# 04_-_RADIO.net
KiCad netlist of a schematic drawn in Altium Designer
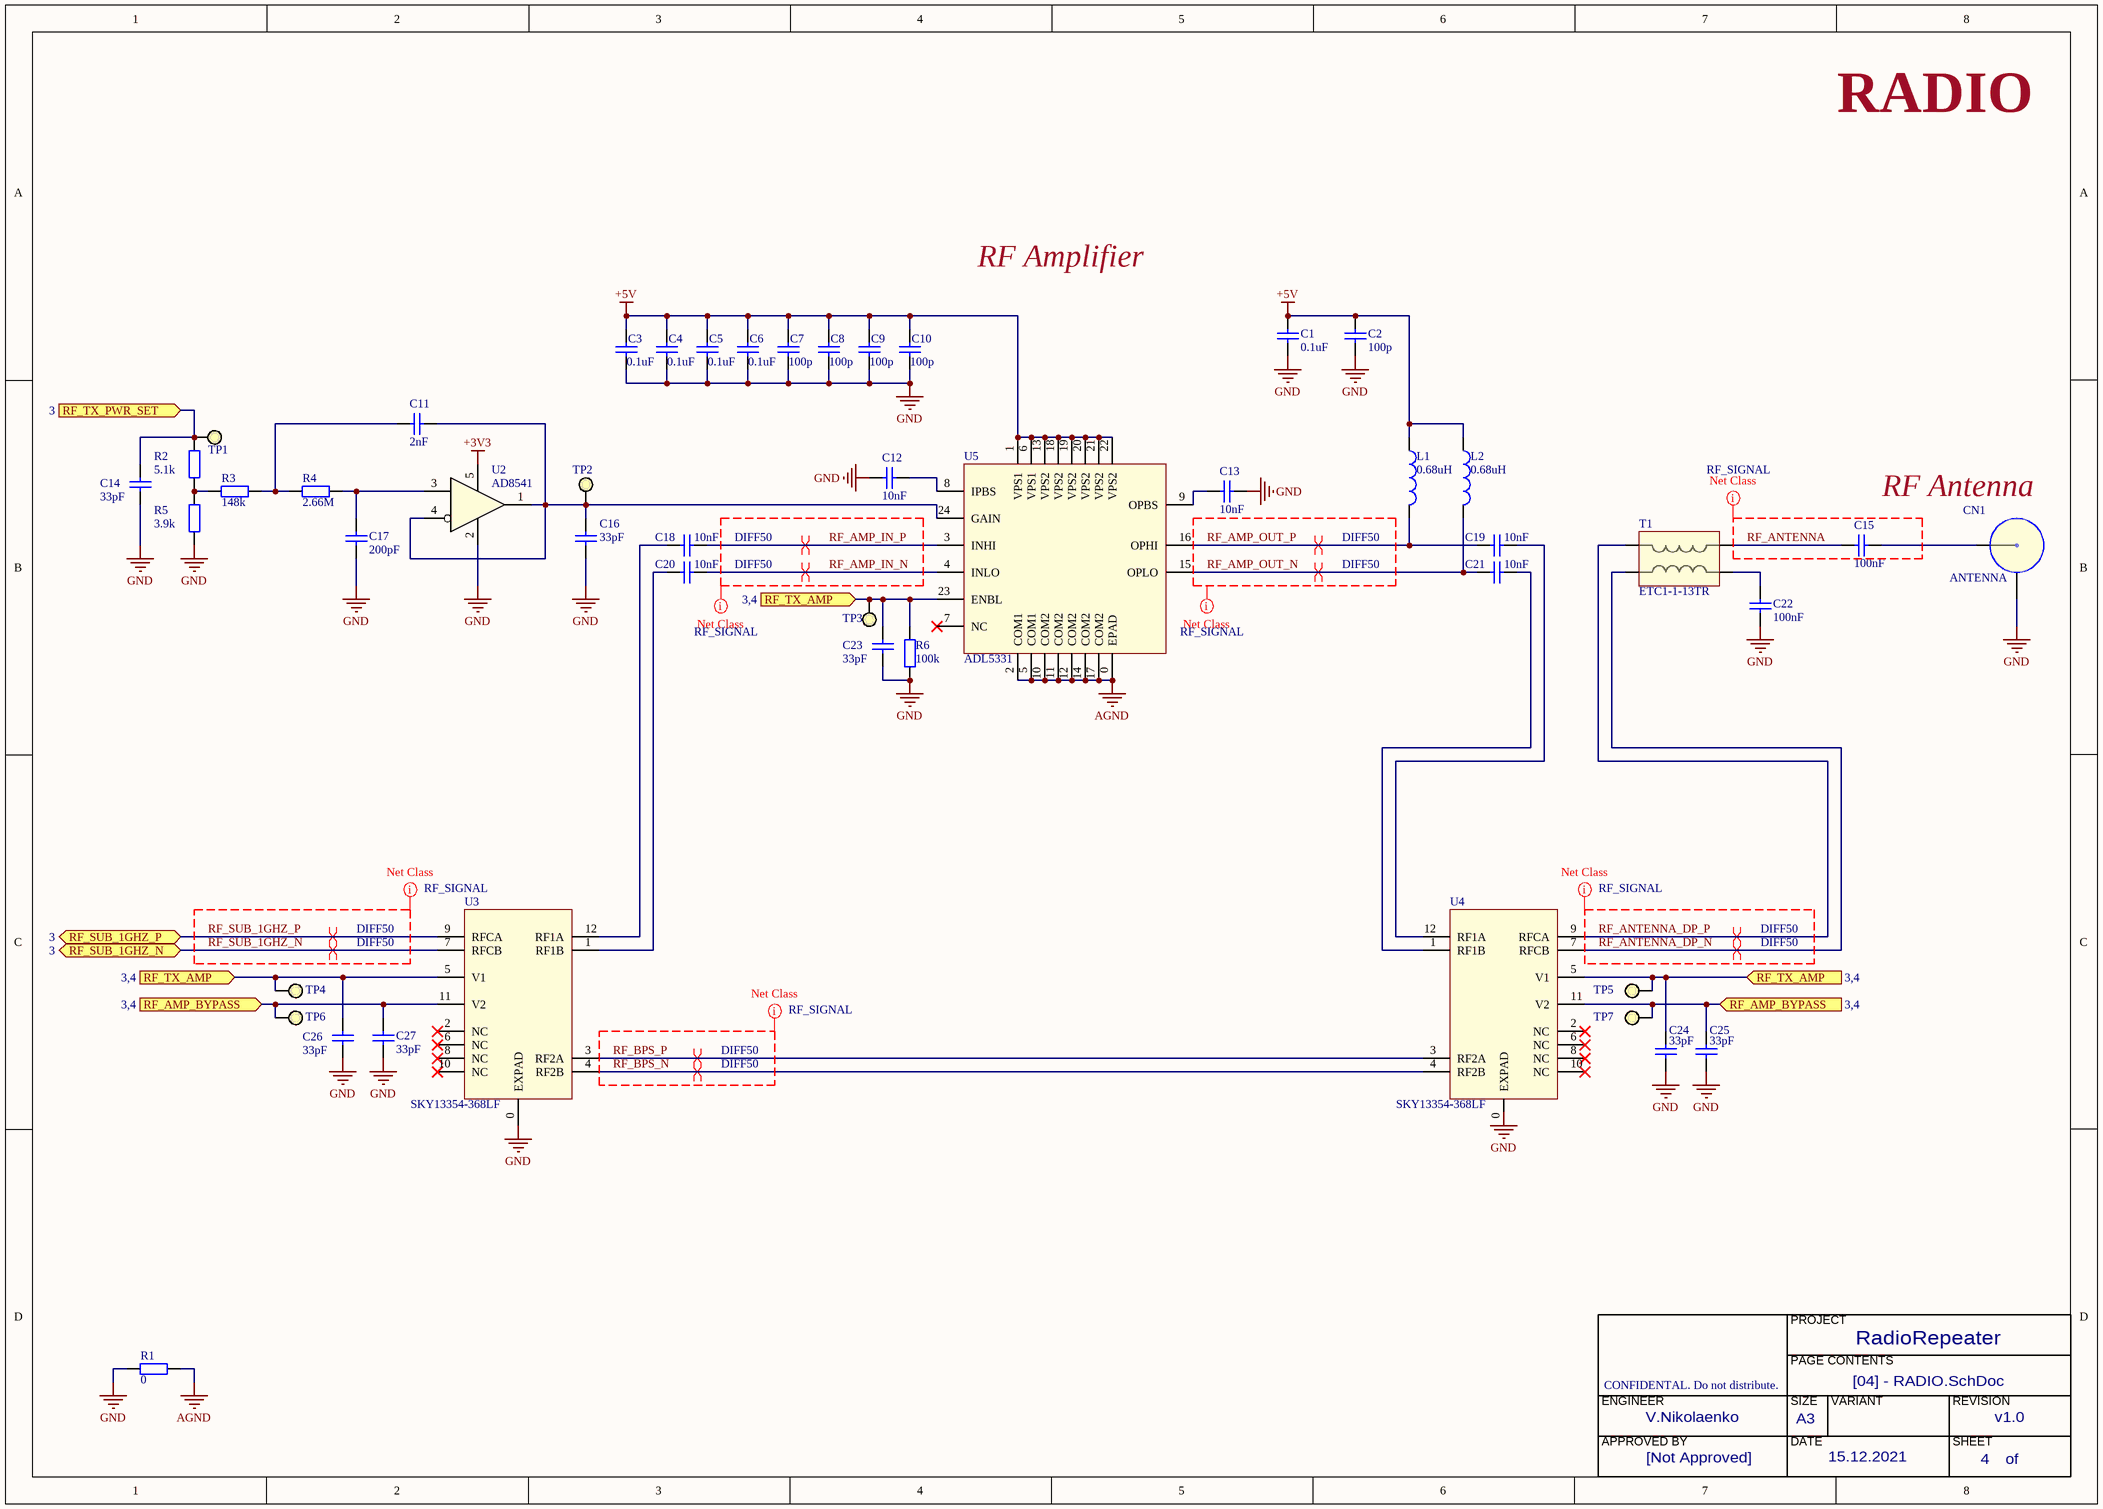
[diagram p0: [04] - RADIO.SchDoc]

(export (version "E")
  (design (tool "Eeschema 10.0.6"))
  (components
    (comp (ref "C1")
      (value "0.1uF")
      (footprint "CAP0402")
      (description "Capacitor")
      (libsource (lib "PASSIVE&DISCRETE") (part "Cap"))
    )
    (comp (ref "C2")
      (value "100p")
      (footprint "CAP0402")
      (description "Capacitor")
      (libsource (lib "PASSIVE&DISCRETE") (part "Cap"))
    )
    (comp (ref "C3")
      (value "0.1uF")
      (footprint "CAP0402")
      (description "Capacitor")
      (libsource (lib "PASSIVE&DISCRETE") (part "Cap"))
    )
    (comp (ref "C4")
      (value "0.1uF")
      (footprint "CAP0402")
      (description "Capacitor")
      (libsource (lib "PASSIVE&DISCRETE") (part "Cap"))
    )
    (comp (ref "C5")
      (value "0.1uF")
      (footprint "CAP0402")
      (description "Capacitor")
      (libsource (lib "PASSIVE&DISCRETE") (part "Cap"))
    )
    (comp (ref "C6")
      (value "0.1uF")
      (footprint "CAP0402")
      (description "Capacitor")
      (libsource (lib "PASSIVE&DISCRETE") (part "Cap"))
    )
    (comp (ref "C7")
      (value "100p")
      (footprint "CAP0402")
      (description "Capacitor")
      (libsource (lib "PASSIVE&DISCRETE") (part "Cap"))
    )
    (comp (ref "C8")
      (value "100p")
      (footprint "CAP0402")
      (description "Capacitor")
      (libsource (lib "PASSIVE&DISCRETE") (part "Cap"))
    )
    (comp (ref "C9")
      (value "100p")
      (footprint "CAP0402")
      (description "Capacitor")
      (libsource (lib "PASSIVE&DISCRETE") (part "Cap"))
    )
    (comp (ref "C10")
      (value "100p")
      (footprint "CAP0402")
      (description "Capacitor")
      (libsource (lib "PASSIVE&DISCRETE") (part "Cap"))
    )
    (comp (ref "C11")
      (value "2nF")
      (footprint "CAP0402")
      (description "Capacitor")
      (libsource (lib "PASSIVE&DISCRETE") (part "Cap"))
    )
    (comp (ref "C12")
      (value "10nF")
      (footprint "CAP0402")
      (description "Capacitor")
      (libsource (lib "PASSIVE&DISCRETE") (part "Cap"))
    )
    (comp (ref "C13")
      (value "10nF")
      (footprint "CAP0402")
      (description "Capacitor")
      (libsource (lib "PASSIVE&DISCRETE") (part "Cap"))
    )
    (comp (ref "C14")
      (value "33pF")
      (footprint "CAP0402")
      (description "Capacitor")
      (libsource (lib "PASSIVE&DISCRETE") (part "Cap"))
    )
    (comp (ref "C15")
      (value "100nF")
      (footprint "CAP0402")
      (description "Capacitor")
      (libsource (lib "PASSIVE&DISCRETE") (part "Cap"))
    )
    (comp (ref "C16")
      (value "33pF")
      (footprint "CAP0402")
      (description "Capacitor")
      (libsource (lib "PASSIVE&DISCRETE") (part "Cap"))
    )
    (comp (ref "C17")
      (value "200pF")
      (footprint "CAP0402")
      (description "Capacitor")
      (libsource (lib "PASSIVE&DISCRETE") (part "Cap"))
    )
    (comp (ref "C18")
      (value "10nF")
      (footprint "CAP0402")
      (description "Capacitor")
      (libsource (lib "PASSIVE&DISCRETE") (part "Cap"))
    )
    (comp (ref "C19")
      (value "10nF")
      (footprint "CAP0402")
      (description "Capacitor")
      (libsource (lib "PASSIVE&DISCRETE") (part "Cap"))
    )
    (comp (ref "C20")
      (value "10nF")
      (footprint "CAP0402")
      (description "Capacitor")
      (libsource (lib "PASSIVE&DISCRETE") (part "Cap"))
    )
    (comp (ref "C21")
      (value "10nF")
      (footprint "CAP0402")
      (description "Capacitor")
      (libsource (lib "PASSIVE&DISCRETE") (part "Cap"))
    )
    (comp (ref "C22")
      (value "100nF")
      (footprint "CAP0402")
      (description "Capacitor")
      (libsource (lib "PASSIVE&DISCRETE") (part "Cap"))
    )
    (comp (ref "C23")
      (value "33pF")
      (footprint "CAP0402")
      (description "Capacitor")
      (libsource (lib "PASSIVE&DISCRETE") (part "Cap"))
    )
    (comp (ref "C24")
      (value "33pF")
      (footprint "CAP0402")
      (description "Capacitor")
      (libsource (lib "PASSIVE&DISCRETE") (part "Cap"))
    )
    (comp (ref "C25")
      (value "33pF")
      (footprint "CAP0402")
      (description "Capacitor")
      (libsource (lib "PASSIVE&DISCRETE") (part "Cap"))
    )
    (comp (ref "C26")
      (value "33pF")
      (footprint "CAP0402")
      (description "Capacitor")
      (libsource (lib "PASSIVE&DISCRETE") (part "Cap"))
    )
    (comp (ref "C27")
      (value "33pF")
      (footprint "CAP0402")
      (description "Capacitor")
      (libsource (lib "PASSIVE&DISCRETE") (part "Cap"))
    )
    (comp (ref "CN1") (value "ANTENNA") (libsource (lib "RadioRepeater") (part "SMC")))
    (comp (ref "L1")
      (value "0.68uH")
      (footprint "INDC0603-0201")
      (description "Inductor")
      (libsource (lib "PASSIVE&DISCRETE") (part "Inductor"))
    )
    (comp (ref "L2")
      (value "0.68uH")
      (footprint "INDC0603-0201")
      (description "Inductor")
      (libsource (lib "PASSIVE&DISCRETE") (part "Inductor"))
    )
    (comp (ref "R1")
      (value "0")
      (footprint "RES0805")
      (description "Resistor")
      (libsource (lib "PASSIVE&DISCRETE") (part "Res"))
    )
    (comp (ref "R2")
      (value "5.1k")
      (footprint "RES0805")
      (description "Resistor")
      (libsource (lib "") (part "Res_1"))
    )
    (comp (ref "R3")
      (value "148k")
      (footprint "RES0805")
      (description "Resistor")
      (libsource (lib "PASSIVE&DISCRETE") (part "Res"))
    )
    (comp (ref "R4")
      (value "2.66M")
      (footprint "RES0805")
      (description "Resistor")
      (libsource (lib "PASSIVE&DISCRETE") (part "Res"))
    )
    (comp (ref "R5")
      (value "3.9k")
      (footprint "RES0805")
      (description "Resistor")
      (libsource (lib "") (part "Res_1"))
    )
    (comp (ref "R6")
      (value "100k")
      (footprint "RES0805")
      (description "Resistor")
      (libsource (lib "") (part "Res_2"))
    )
    (comp (ref "T1") (value "ETC1-1-13TR") (libsource (lib "RadioRepeater") (part "balun_0433BM15A0001E")))
    (comp (ref "TP1")
      (value "TestPoint")
      (footprint "TestPoint")
      (libsource (lib "CONNECTORS") (part "TestPoint"))
    )
    (comp (ref "TP2")
      (value "TestPoint")
      (footprint "TestPoint")
      (libsource (lib "CONNECTORS") (part "TestPoint"))
    )
    (comp (ref "TP3")
      (value "TestPoint")
      (footprint "TestPoint")
      (libsource (lib "CONNECTORS") (part "TestPoint"))
    )
    (comp (ref "TP4")
      (value "TestPoint")
      (footprint "TestPoint")
      (libsource (lib "CONNECTORS") (part "TestPoint"))
    )
    (comp (ref "TP5")
      (value "TestPoint")
      (footprint "TestPoint")
      (libsource (lib "CONNECTORS") (part "TestPoint"))
    )
    (comp (ref "TP6")
      (value "TestPoint")
      (footprint "TestPoint")
      (libsource (lib "CONNECTORS") (part "TestPoint"))
    )
    (comp (ref "TP7")
      (value "TestPoint")
      (footprint "TestPoint")
      (libsource (lib "CONNECTORS") (part "TestPoint"))
    )
    (comp (ref "U2")
      (value "AD8541")
      (footprint "SOT23-5_PITCH0.95")
      (libsource (lib "MISCELLANEOUS") (part "OPAMP x1"))
    )
    (comp (ref "U3") (value "SKY13354-368LF") (libsource (lib "") (part "SKY13354-368LF_1")))
    (comp (ref "U4") (value "SKY13354-368LF") (libsource (lib "RadioRepeater") (part "SKY13354-368LF")))
    (comp (ref "U5") (value "ADL5331") (libsource (lib "RadioRepeater") (part "ADL5331")))
  )
  (nets
    (net (code "1") (name "+3V3") (class "Default")
      (node (ref "U2") (pin "5") (pinfunction "VCC+_5") (pintype "passive"))
    )
    (net (code "2") (name "+5V") (class "Default")
      (node (ref "C1") (pin "1") (pinfunction "1_1") (pintype "passive"))
      (node (ref "C10") (pin "1") (pinfunction "1_1") (pintype "passive"))
      (node (ref "C2") (pin "1") (pinfunction "1_1") (pintype "passive"))
      (node (ref "C3") (pin "1") (pinfunction "1_1") (pintype "passive"))
      (node (ref "C4") (pin "1") (pinfunction "1_1") (pintype "passive"))
      (node (ref "C5") (pin "1") (pinfunction "1_1") (pintype "passive"))
      (node (ref "C6") (pin "1") (pinfunction "1_1") (pintype "passive"))
      (node (ref "C7") (pin "1") (pinfunction "1_1") (pintype "passive"))
      (node (ref "C8") (pin "1") (pinfunction "1_1") (pintype "passive"))
      (node (ref "C9") (pin "1") (pinfunction "1_1") (pintype "passive"))
      (node (ref "L1") (pin "1") (pinfunction "1_1") (pintype "passive"))
      (node (ref "L2") (pin "1") (pinfunction "1_1") (pintype "passive"))
      (node (ref "U5") (pin "1") (pinfunction "VPS1_1") (pintype "passive"))
      (node (ref "U5") (pin "13") (pinfunction "VPS2_13") (pintype "passive"))
      (node (ref "U5") (pin "18") (pinfunction "VPS2_18") (pintype "passive"))
      (node (ref "U5") (pin "19") (pinfunction "VPS2_19") (pintype "passive"))
      (node (ref "U5") (pin "20") (pinfunction "VPS2_20") (pintype "passive"))
      (node (ref "U5") (pin "21") (pinfunction "VPS2_21") (pintype "passive"))
      (node (ref "U5") (pin "22") (pinfunction "VPS2_22") (pintype "passive"))
      (node (ref "U5") (pin "6") (pinfunction "VPS1_6") (pintype "passive"))
    )
    (net (code "3") (name "/RF_AMP_BYPASS") (class "Default")
      (node (ref "C25") (pin "2") (pinfunction "2_2") (pintype "passive"))
      (node (ref "C27") (pin "2") (pinfunction "2_2") (pintype "passive"))
      (node (ref "TP6") (pin "1") (pinfunction "1_1") (pintype "passive"))
      (node (ref "TP7") (pin "1") (pinfunction "1_1") (pintype "passive"))
      (node (ref "U3") (pin "11") (pinfunction "V2_11") (pintype "passive"))
      (node (ref "U4") (pin "11") (pinfunction "V2_11") (pintype "passive"))
    )
    (net (code "4") (name "/RF_AMP_IN_N") (class "Default")
      (node (ref "C20") (pin "1") (pinfunction "1_1") (pintype "passive"))
      (node (ref "U5") (pin "4") (pinfunction "INLO_4") (pintype "passive"))
    )
    (net (code "5") (name "/RF_AMP_IN_P") (class "Default")
      (node (ref "C18") (pin "1") (pinfunction "1_1") (pintype "passive"))
      (node (ref "U5") (pin "3") (pinfunction "INHI_3") (pintype "passive"))
    )
    (net (code "6") (name "/RF_AMP_OUT_N") (class "Default")
      (node (ref "C21") (pin "2") (pinfunction "2_2") (pintype "passive"))
      (node (ref "L2") (pin "2") (pinfunction "2_2") (pintype "passive"))
      (node (ref "U5") (pin "15") (pinfunction "OPLO_15") (pintype "passive"))
    )
    (net (code "7") (name "/RF_AMP_OUT_P") (class "Default")
      (node (ref "C19") (pin "2") (pinfunction "2_2") (pintype "passive"))
      (node (ref "L1") (pin "2") (pinfunction "2_2") (pintype "passive"))
      (node (ref "U5") (pin "16") (pinfunction "OPHI_16") (pintype "passive"))
    )
    (net (code "8") (name "/RF_ANTENNA") (class "Default")
      (node (ref "C15") (pin "2") (pinfunction "2_2") (pintype "passive"))
      (node (ref "T1") (pin "1") (pinfunction "UP_1") (pintype "passive"))
    )
    (net (code "9") (name "/RF_ANTENNA_DP_N") (class "Default")
      (node (ref "T1") (pin "4") (pinfunction "BP_4") (pintype "passive"))
      (node (ref "U4") (pin "7") (pinfunction "RFCB_7") (pintype "passive"))
    )
    (net (code "10") (name "/RF_ANTENNA_DP_P") (class "Default")
      (node (ref "T1") (pin "3") (pinfunction "BP_3") (pintype "passive"))
      (node (ref "U4") (pin "9") (pinfunction "RFCA_9") (pintype "passive"))
    )
    (net (code "11") (name "/RF_BPS_N") (class "Default")
      (node (ref "U3") (pin "4") (pinfunction "RF2B_4") (pintype "passive"))
      (node (ref "U4") (pin "4") (pinfunction "RF2B_4") (pintype "passive"))
    )
    (net (code "12") (name "/RF_BPS_P") (class "Default")
      (node (ref "U3") (pin "3") (pinfunction "RF2A_3") (pintype "passive"))
      (node (ref "U4") (pin "3") (pinfunction "RF2A_3") (pintype "passive"))
    )
    (net (code "13") (name "/RF_SUB_1GHZ_N") (class "Default")
      (node (ref "U3") (pin "7") (pinfunction "RFCB_7") (pintype "passive"))
    )
    (net (code "14") (name "/RF_SUB_1GHZ_P") (class "Default")
      (node (ref "U3") (pin "9") (pinfunction "RFCA_9") (pintype "passive"))
    )
    (net (code "15") (name "/RF_TX_AMP") (class "Default")
      (node (ref "C23") (pin "2") (pinfunction "2_2") (pintype "passive"))
      (node (ref "C24") (pin "2") (pinfunction "2_2") (pintype "passive"))
      (node (ref "C26") (pin "2") (pinfunction "2_2") (pintype "passive"))
      (node (ref "R6") (pin "2") (pinfunction "2_2") (pintype "passive"))
      (node (ref "TP3") (pin "1") (pinfunction "1_1") (pintype "passive"))
      (node (ref "TP4") (pin "1") (pinfunction "1_1") (pintype "passive"))
      (node (ref "TP5") (pin "1") (pinfunction "1_1") (pintype "passive"))
      (node (ref "U3") (pin "5") (pinfunction "V1_5") (pintype "passive"))
      (node (ref "U4") (pin "5") (pinfunction "V1_5") (pintype "passive"))
      (node (ref "U5") (pin "23") (pinfunction "ENBL_23") (pintype "passive"))
    )
    (net (code "16") (name "/RF_TX_PWR_SET") (class "Default")
      (node (ref "C14") (pin "2") (pinfunction "2_2") (pintype "passive"))
      (node (ref "R2") (pin "1") (pinfunction "1_1") (pintype "passive"))
      (node (ref "TP1") (pin "1") (pinfunction "1_1") (pintype "passive"))
    )
    (net (code "17") (name "AGND") (class "Default")
      (node (ref "R1") (pin "1") (pinfunction "1_1") (pintype "passive"))
      (node (ref "U5") (pin "0") (pinfunction "EPAD_0") (pintype "passive"))
      (node (ref "U5") (pin "10") (pinfunction "COM2_10") (pintype "passive"))
      (node (ref "U5") (pin "11") (pinfunction "COM2_11") (pintype "passive"))
      (node (ref "U5") (pin "12") (pinfunction "COM2_12") (pintype "passive"))
      (node (ref "U5") (pin "14") (pinfunction "COM2_14") (pintype "passive"))
      (node (ref "U5") (pin "17") (pinfunction "COM2_17") (pintype "passive"))
      (node (ref "U5") (pin "2") (pinfunction "COM1_2") (pintype "passive"))
      (node (ref "U5") (pin "5") (pinfunction "COM1_5") (pintype "passive"))
    )
    (net (code "18") (name "GND") (class "Default")
      (node (ref "C1") (pin "2") (pinfunction "2_2") (pintype "passive"))
      (node (ref "C10") (pin "2") (pinfunction "2_2") (pintype "passive"))
      (node (ref "C12") (pin "1") (pinfunction "1_1") (pintype "passive"))
      (node (ref "C13") (pin "1") (pinfunction "1_1") (pintype "passive"))
      (node (ref "C14") (pin "1") (pinfunction "1_1") (pintype "passive"))
      (node (ref "C16") (pin "1") (pinfunction "1_1") (pintype "passive"))
      (node (ref "C17") (pin "1") (pinfunction "1_1") (pintype "passive"))
      (node (ref "C2") (pin "2") (pinfunction "2_2") (pintype "passive"))
      (node (ref "C22") (pin "1") (pinfunction "1_1") (pintype "passive"))
      (node (ref "C23") (pin "1") (pinfunction "1_1") (pintype "passive"))
      (node (ref "C24") (pin "1") (pinfunction "1_1") (pintype "passive"))
      (node (ref "C25") (pin "1") (pinfunction "1_1") (pintype "passive"))
      (node (ref "C26") (pin "1") (pinfunction "1_1") (pintype "passive"))
      (node (ref "C27") (pin "1") (pinfunction "1_1") (pintype "passive"))
      (node (ref "C3") (pin "2") (pinfunction "2_2") (pintype "passive"))
      (node (ref "C4") (pin "2") (pinfunction "2_2") (pintype "passive"))
      (node (ref "C5") (pin "2") (pinfunction "2_2") (pintype "passive"))
      (node (ref "C6") (pin "2") (pinfunction "2_2") (pintype "passive"))
      (node (ref "C7") (pin "2") (pinfunction "2_2") (pintype "passive"))
      (node (ref "C8") (pin "2") (pinfunction "2_2") (pintype "passive"))
      (node (ref "C9") (pin "2") (pinfunction "2_2") (pintype "passive"))
      (node (ref "CN1") (pin "14") (pinfunction "14_14") (pintype "passive"))
      (node (ref "R1") (pin "2") (pinfunction "2_2") (pintype "passive"))
      (node (ref "R5") (pin "2") (pinfunction "2_2") (pintype "passive"))
      (node (ref "R6") (pin "1") (pinfunction "1_1") (pintype "passive"))
      (node (ref "U2") (pin "2") (pinfunction "VCC-_2") (pintype "passive"))
      (node (ref "U3") (pin "0") (pinfunction "EXPAD_0") (pintype "passive"))
    )
    (net (code "19") (name "Net-(C11-Pad2)") (class "Default")
      (node (ref "C11") (pin "2") (pinfunction "2_2") (pintype "passive"))
      (node (ref "R3") (pin "1") (pinfunction "1_1") (pintype "passive"))
      (node (ref "R4") (pin "2") (pinfunction "2_2") (pintype "passive"))
    )
    (net (code "20") (name "Net-(C15-Pad1)") (class "Default")
      (node (ref "C15") (pin "1") (pinfunction "1_1") (pintype "passive"))
      (node (ref "CN1") (pin "14") (pinfunction "14_14") (pintype "passive"))
    )
    (net (code "21") (name "Net-(R2-Pad2)") (class "Default")
      (node (ref "R2") (pin "2") (pinfunction "2_2") (pintype "passive"))
      (node (ref "R3") (pin "2") (pinfunction "2_2") (pintype "passive"))
      (node (ref "R5") (pin "1") (pinfunction "1_1") (pintype "passive"))
    )
    (net (code "22") (name "Net-(T1-GND)") (class "Default")
      (node (ref "C22") (pin "2") (pinfunction "2_2") (pintype "passive"))
      (node (ref "T1") (pin "2") (pinfunction "GND_2") (pintype "passive"))
    )
    (net (code "23") (name "Net-(U2-IN+)") (class "Default")
      (node (ref "C17") (pin "2") (pinfunction "2_2") (pintype "passive"))
      (node (ref "R4") (pin "1") (pinfunction "1_1") (pintype "passive"))
      (node (ref "U2") (pin "3") (pinfunction "IN+_3") (pintype "passive"))
    )
    (net (code "24") (name "Net-(U2-IN-)") (class "Default")
      (node (ref "C11") (pin "1") (pinfunction "1_1") (pintype "passive"))
      (node (ref "C16") (pin "2") (pinfunction "2_2") (pintype "passive"))
      (node (ref "TP2") (pin "1") (pinfunction "1_1") (pintype "passive"))
      (node (ref "U2") (pin "1") (pinfunction "OUT_1") (pintype "passive"))
      (node (ref "U2") (pin "4") (pinfunction "IN-_4") (pintype "passive"))
      (node (ref "U5") (pin "24") (pinfunction "GAIN_24") (pintype "passive"))
    )
    (net (code "25") (name "Net-(U3-RF1A)") (class "Default")
      (node (ref "C18") (pin "2") (pinfunction "2_2") (pintype "passive"))
      (node (ref "U3") (pin "12") (pinfunction "RF1A_12") (pintype "passive"))
    )
    (net (code "26") (name "Net-(U3-RF1B)") (class "Default")
      (node (ref "C20") (pin "2") (pinfunction "2_2") (pintype "passive"))
      (node (ref "U3") (pin "1") (pinfunction "RF1B_1") (pintype "passive"))
    )
    (net (code "27") (name "Net-(U4-RF1A)") (class "Default")
      (node (ref "C19") (pin "1") (pinfunction "1_1") (pintype "passive"))
      (node (ref "U4") (pin "12") (pinfunction "RF1A_12") (pintype "passive"))
    )
    (net (code "28") (name "Net-(U4-RF1B)") (class "Default")
      (node (ref "C21") (pin "1") (pinfunction "1_1") (pintype "passive"))
      (node (ref "U4") (pin "1") (pinfunction "RF1B_1") (pintype "passive"))
    )
    (net (code "29") (name "Net-(U5-IPBS)") (class "Default")
      (node (ref "C12") (pin "2") (pinfunction "2_2") (pintype "passive"))
      (node (ref "U5") (pin "8") (pinfunction "IPBS_8") (pintype "passive"))
    )
    (net (code "30") (name "Net-(U5-OPBS)") (class "Default")
      (node (ref "C13") (pin "2") (pinfunction "2_2") (pintype "passive"))
      (node (ref "U5") (pin "9") (pinfunction "OPBS_9") (pintype "passive"))
    )
    (net (code "31") (name "unconnected-(U3-NC-Pad2)") (class "Default")
      (node (ref "U3") (pin "2") (pinfunction "NC_2") (pintype "passive+no_connect"))
    )
    (net (code "32") (name "unconnected-(U3-NC-Pad6)") (class "Default")
      (node (ref "U3") (pin "6") (pinfunction "NC_6") (pintype "passive+no_connect"))
    )
    (net (code "33") (name "unconnected-(U3-NC-Pad8)") (class "Default")
      (node (ref "U3") (pin "8") (pinfunction "NC_8") (pintype "passive+no_connect"))
    )
    (net (code "34") (name "unconnected-(U3-NC-Pad10)") (class "Default")
      (node (ref "U3") (pin "10") (pinfunction "NC_10") (pintype "passive+no_connect"))
    )
    (net (code "35") (name "unconnected-(U4-EXPAD-Pad0)") (class "Default")
      (node (ref "U4") (pin "0") (pinfunction "EXPAD_0") (pintype "passive"))
    )
    (net (code "36") (name "unconnected-(U4-NC-Pad2)") (class "Default")
      (node (ref "U4") (pin "2") (pinfunction "NC_2") (pintype "passive+no_connect"))
    )
    (net (code "37") (name "unconnected-(U4-NC-Pad6)") (class "Default")
      (node (ref "U4") (pin "6") (pinfunction "NC_6") (pintype "passive+no_connect"))
    )
    (net (code "38") (name "unconnected-(U4-NC-Pad8)") (class "Default")
      (node (ref "U4") (pin "8") (pinfunction "NC_8") (pintype "passive+no_connect"))
    )
    (net (code "39") (name "unconnected-(U4-NC-Pad10)") (class "Default")
      (node (ref "U4") (pin "10") (pinfunction "NC_10") (pintype "passive+no_connect"))
    )
    (net (code "40") (name "unconnected-(U5-NC-Pad7)") (class "Default")
      (node (ref "U5") (pin "7") (pinfunction "NC_7") (pintype "passive+no_connect"))
    )
  )
)
